# WiFi_module_main.net
KiCad netlist of a schematic drawn in Altium Designer
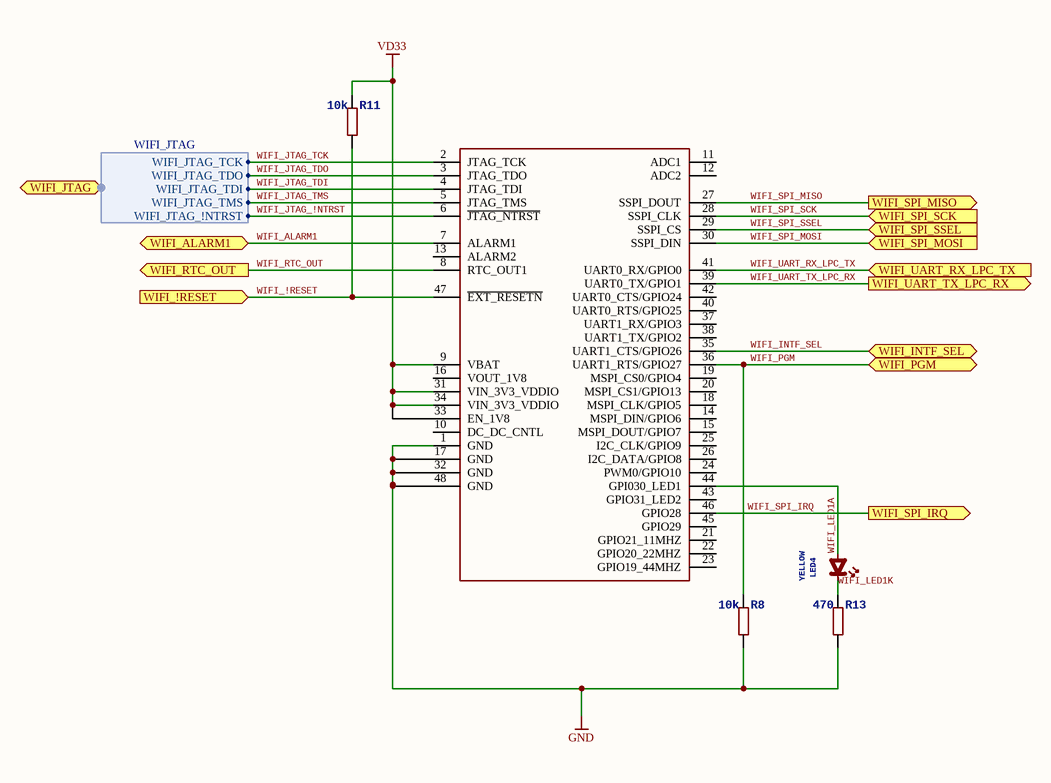
[diagram p0: WiFi_module_main.SchDoc]

(export (version "E")
  (design (tool "Eeschema 10.0.6"))
  (components
    (comp (ref "LED4")
      (value "YELLOW")
      (footprint "0402_POLAR")
      (description "LED common")
      (libsource (lib "WunderBar_v101") (part "LED0402"))
    )
    (comp (ref "R8")
      (value "10k")
      (footprint "0402")
      (description "RESISTOR")
      (libsource (lib "WunderBar_v101") (part "R-EU_0402"))
    )
    (comp (ref "R11")
      (value "10k")
      (footprint "0402")
      (description "RESISTOR")
      (libsource (lib "WunderBar_v101") (part "R-EU_0402"))
    )
    (comp (ref "R13")
      (value "470")
      (footprint "0402")
      (description "RESISTOR")
      (libsource (lib "WunderBar_v101") (part "R-EU_0402"))
    )
    (comp (ref "WIFI")
      (value "GS1500M")
      (footprint "GAINSPANM")
      (description "GAINSPAN WiFi module")
      (libsource (lib "WunderBar_v101") (part "GAINSPAN1500MXXGAINSPANMEXP"))
    )
  )
  (nets
    (net (code "2") (name "/WIFI_!RESET") (class "Default")
      (node (ref "R11") (pin "1") (pinfunction "1_1") (pintype "passive"))
      (node (ref "WIFI") (pin "47") (pinfunction "~{EXT_RESETN}_47") (pintype "passive"))
    )
    (net (code "3") (name "/WIFI_ALARM1") (class "Default")
      (node (ref "WIFI") (pin "7") (pinfunction "ALARM1_7") (pintype "passive"))
    )
    (net (code "4") (name "/WIFI_INTF_SEL") (class "Default")
      (node (ref "WIFI") (pin "35") (pinfunction "UART1_CTS/GPIO26_35") (pintype "passive"))
    )
    (net (code "5") (name "/WIFI_JTAG_!NTRST") (class "Default")
      (node (ref "WIFI") (pin "6") (pinfunction "~{JTAG_NTRST}_6") (pintype "passive"))
    )
    (net (code "6") (name "/WIFI_JTAG_TCK") (class "Default")
      (node (ref "WIFI") (pin "2") (pinfunction "JTAG_TCK_2") (pintype "passive"))
    )
    (net (code "7") (name "/WIFI_JTAG_TDI") (class "Default")
      (node (ref "WIFI") (pin "4") (pinfunction "JTAG_TDI_4") (pintype "passive"))
    )
    (net (code "8") (name "/WIFI_JTAG_TDO") (class "Default")
      (node (ref "WIFI") (pin "3") (pinfunction "JTAG_TDO_3") (pintype "passive"))
    )
    (net (code "9") (name "/WIFI_JTAG_TMS") (class "Default")
      (node (ref "WIFI") (pin "5") (pinfunction "JTAG_TMS_5") (pintype "passive"))
    )
    (net (code "10") (name "/WIFI_LED1A") (class "Default")
      (node (ref "LED4") (pin "A") (pinfunction "ANODE_A") (pintype "passive"))
      (node (ref "WIFI") (pin "44") (pinfunction "GPI030_LED1_44") (pintype "passive"))
    )
    (net (code "11") (name "/WIFI_LED1K") (class "Default")
      (node (ref "LED4") (pin "K") (pinfunction "CATHODE_K") (pintype "passive"))
      (node (ref "R13") (pin "2") (pinfunction "2_2") (pintype "passive"))
    )
    (net (code "12") (name "/WIFI_PGM") (class "Default")
      (node (ref "R8") (pin "2") (pinfunction "2_2") (pintype "passive"))
      (node (ref "WIFI") (pin "36") (pinfunction "UART1_RTS/GPIO27_36") (pintype "passive"))
    )
    (net (code "13") (name "/WIFI_RTC_OUT") (class "Default")
      (node (ref "WIFI") (pin "8") (pinfunction "RTC_OUT1_8") (pintype "passive"))
    )
    (net (code "14") (name "/WIFI_SPI_IRQ") (class "Default")
      (node (ref "WIFI") (pin "46") (pinfunction "GPIO28_46") (pintype "passive"))
    )
    (net (code "15") (name "/WIFI_SPI_MISO") (class "Default")
      (node (ref "WIFI") (pin "27") (pinfunction "SSPI_DOUT_27") (pintype "passive"))
    )
    (net (code "16") (name "/WIFI_SPI_MOSI") (class "Default")
      (node (ref "WIFI") (pin "30") (pinfunction "SSPI_DIN_30") (pintype "passive"))
    )
    (net (code "17") (name "/WIFI_SPI_SCK") (class "Default")
      (node (ref "WIFI") (pin "28") (pinfunction "SSPI_CLK_28") (pintype "passive"))
    )
    (net (code "18") (name "/WIFI_SPI_SSEL") (class "Default")
      (node (ref "WIFI") (pin "29") (pinfunction "SSPI_CS_29") (pintype "passive"))
    )
    (net (code "19") (name "/WIFI_UART_RX_LPC_TX") (class "Default")
      (node (ref "WIFI") (pin "41") (pinfunction "UART0_RX/GPIO0_41") (pintype "passive"))
    )
    (net (code "20") (name "/WIFI_UART_TX_LPC_RX") (class "Default")
      (node (ref "WIFI") (pin "39") (pinfunction "UART0_TX/GPIO1_39") (pintype "passive"))
    )
    (net (code "22") (name "GND") (class "Default")
      (node (ref "R13") (pin "1") (pinfunction "1_1") (pintype "passive"))
      (node (ref "R8") (pin "1") (pinfunction "1_1") (pintype "passive"))
      (node (ref "WIFI") (pin "1") (pinfunction "GND_1") (pintype "passive"))
      (node (ref "WIFI") (pin "17") (pinfunction "GND_17") (pintype "passive"))
      (node (ref "WIFI") (pin "32") (pinfunction "GND_32") (pintype "passive"))
      (node (ref "WIFI") (pin "48") (pinfunction "GND_48") (pintype "passive"))
    )
    (net (code "23") (name "VD33") (class "Default")
      (node (ref "R11") (pin "2") (pinfunction "2_2") (pintype "passive"))
      (node (ref "WIFI") (pin "31") (pinfunction "VIN_3V3_VDDIO_31") (pintype "passive"))
      (node (ref "WIFI") (pin "33") (pinfunction "EN_1V8_33") (pintype "passive"))
      (node (ref "WIFI") (pin "34") (pinfunction "VIN_3V3_VDDIO_34") (pintype "passive"))
      (node (ref "WIFI") (pin "9") (pinfunction "VBAT_9") (pintype "passive"))
    )
    (net (code "24") (name "unconnected-(WIFI-ADC1-Pad11)") (class "Default")
      (node (ref "WIFI") (pin "11") (pinfunction "ADC1_11") (pintype "passive"))
    )
    (net (code "25") (name "unconnected-(WIFI-ADC2-Pad12)") (class "Default")
      (node (ref "WIFI") (pin "12") (pinfunction "ADC2_12") (pintype "passive"))
    )
    (net (code "26") (name "unconnected-(WIFI-ALARM2-Pad13)") (class "Default")
      (node (ref "WIFI") (pin "13") (pinfunction "ALARM2_13") (pintype "passive"))
    )
    (net (code "27") (name "unconnected-(WIFI-DC_DC_CNTL-Pad10)") (class "Default")
      (node (ref "WIFI") (pin "10") (pinfunction "DC_DC_CNTL_10") (pintype "passive"))
    )
    (net (code "28") (name "unconnected-(WIFI-GPIO19_44MHZ-Pad23)") (class "Default")
      (node (ref "WIFI") (pin "23") (pinfunction "GPIO19_44MHZ_23") (pintype "passive"))
    )
    (net (code "29") (name "unconnected-(WIFI-GPIO20_22MHZ-Pad22)") (class "Default")
      (node (ref "WIFI") (pin "22") (pinfunction "GPIO20_22MHZ_22") (pintype "passive"))
    )
    (net (code "30") (name "unconnected-(WIFI-GPIO21_11MHZ-Pad21)") (class "Default")
      (node (ref "WIFI") (pin "21") (pinfunction "GPIO21_11MHZ_21") (pintype "passive"))
    )
    (net (code "31") (name "unconnected-(WIFI-GPIO29-Pad45)") (class "Default")
      (node (ref "WIFI") (pin "45") (pinfunction "GPIO29_45") (pintype "passive"))
    )
    (net (code "32") (name "unconnected-(WIFI-GPIO31_LED2-Pad43)") (class "Default")
      (node (ref "WIFI") (pin "43") (pinfunction "GPIO31_LED2_43") (pintype "passive"))
    )
    (net (code "33") (name "unconnected-(WIFI-I2C_CLK{slash}GPIO9-Pad25)") (class "Default")
      (node (ref "WIFI") (pin "25") (pinfunction "I2C_CLK/GPIO9_25") (pintype "passive"))
    )
    (net (code "34") (name "unconnected-(WIFI-I2C_DATA{slash}GPIO8-Pad26)") (class "Default")
      (node (ref "WIFI") (pin "26") (pinfunction "I2C_DATA/GPIO8_26") (pintype "passive"))
    )
    (net (code "35") (name "unconnected-(WIFI-MSPI_CLK{slash}GPIO5-Pad18)") (class "Default")
      (node (ref "WIFI") (pin "18") (pinfunction "MSPI_CLK/GPIO5_18") (pintype "passive"))
    )
    (net (code "36") (name "unconnected-(WIFI-MSPI_CS0{slash}GPIO4-Pad19)") (class "Default")
      (node (ref "WIFI") (pin "19") (pinfunction "MSPI_CS0/GPIO4_19") (pintype "passive"))
    )
    (net (code "37") (name "unconnected-(WIFI-MSPI_CS1{slash}GPIO13-Pad20)") (class "Default")
      (node (ref "WIFI") (pin "20") (pinfunction "MSPI_CS1/GPIO13_20") (pintype "passive"))
    )
    (net (code "38") (name "unconnected-(WIFI-MSPI_DIN{slash}GPIO6-Pad14)") (class "Default")
      (node (ref "WIFI") (pin "14") (pinfunction "MSPI_DIN/GPIO6_14") (pintype "passive"))
    )
    (net (code "39") (name "unconnected-(WIFI-MSPI_DOUT{slash}GPIO7-Pad15)") (class "Default")
      (node (ref "WIFI") (pin "15") (pinfunction "MSPI_DOUT/GPIO7_15") (pintype "passive"))
    )
    (net (code "40") (name "unconnected-(WIFI-PWM0{slash}GPIO10-Pad24)") (class "Default")
      (node (ref "WIFI") (pin "24") (pinfunction "PWM0/GPIO10_24") (pintype "passive"))
    )
    (net (code "41") (name "unconnected-(WIFI-UART0_CTS{slash}GPIO24-Pad42)") (class "Default")
      (node (ref "WIFI") (pin "42") (pinfunction "UART0_CTS/GPIO24_42") (pintype "passive"))
    )
    (net (code "42") (name "unconnected-(WIFI-UART0_RTS{slash}GPIO25-Pad40)") (class "Default")
      (node (ref "WIFI") (pin "40") (pinfunction "UART0_RTS/GPIO25_40") (pintype "passive"))
    )
    (net (code "43") (name "unconnected-(WIFI-UART1_RX{slash}GPIO3-Pad37)") (class "Default")
      (node (ref "WIFI") (pin "37") (pinfunction "UART1_RX/GPIO3_37") (pintype "passive"))
    )
    (net (code "44") (name "unconnected-(WIFI-UART1_TX{slash}GPIO2-Pad38)") (class "Default")
      (node (ref "WIFI") (pin "38") (pinfunction "UART1_TX/GPIO2_38") (pintype "passive"))
    )
    (net (code "45") (name "unconnected-(WIFI-VOUT_1V8-Pad16)") (class "Default")
      (node (ref "WIFI") (pin "16") (pinfunction "VOUT_1V8_16") (pintype "passive"))
    )
  )
)
